# Cyclone-Pulse-Wrangler-Mainboard.net
KiCad netlist of a schematic drawn in EAGLE
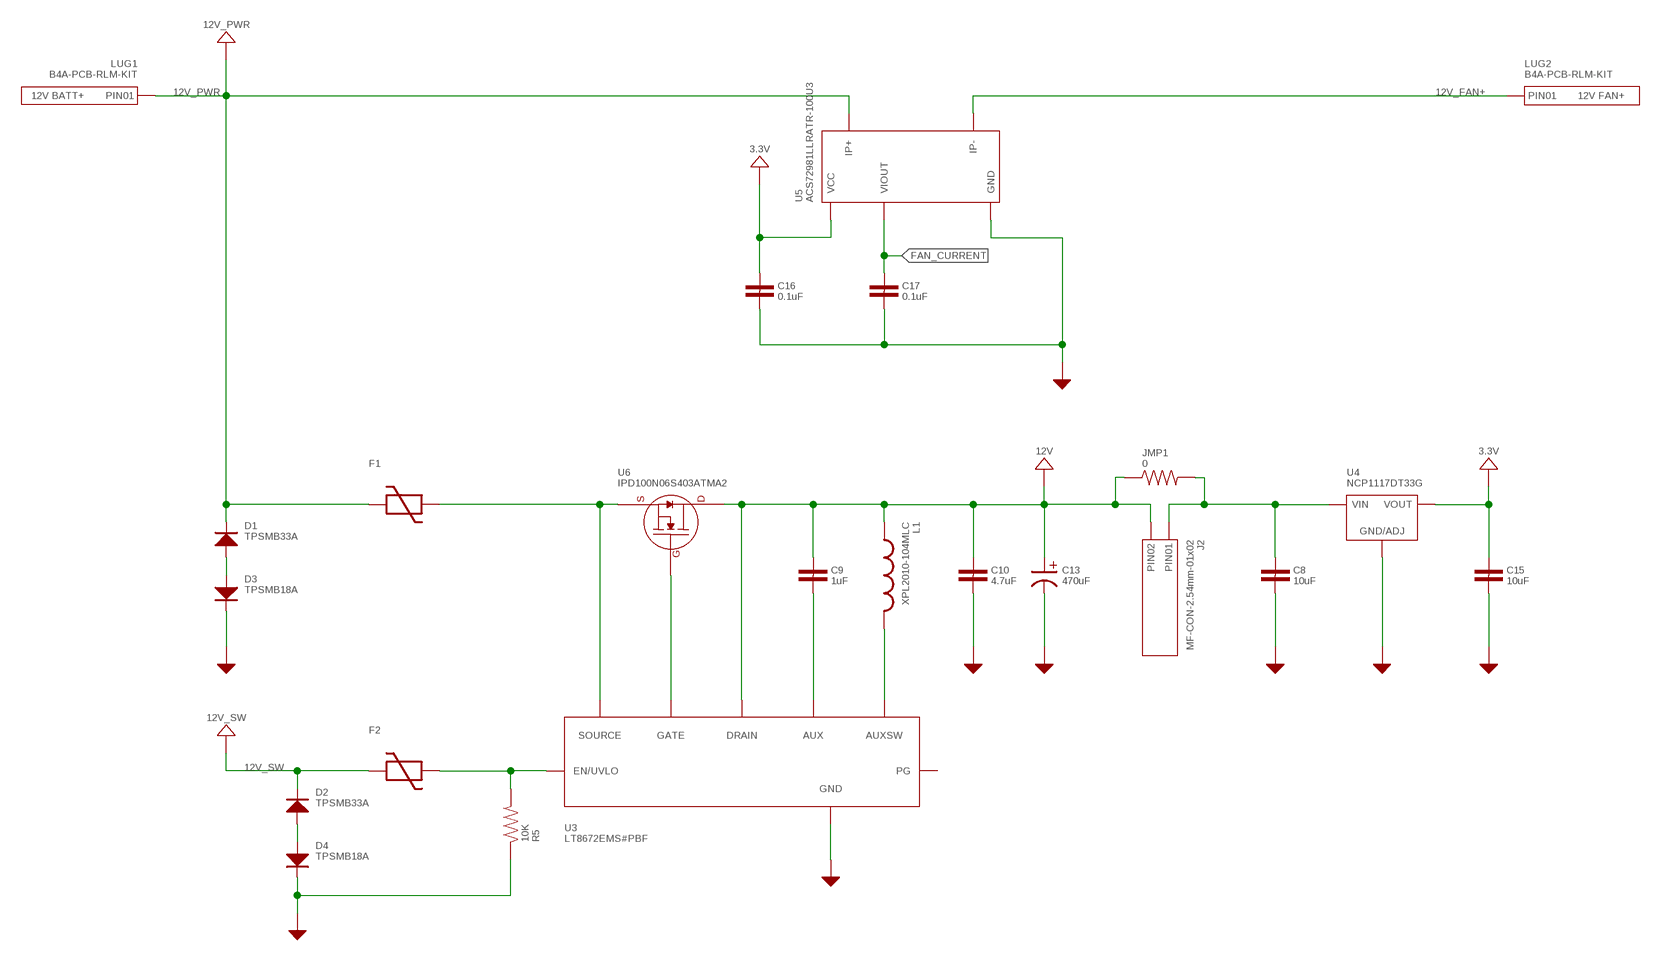
[diagram p0: schematic, sheet 1, part 1 of 3]
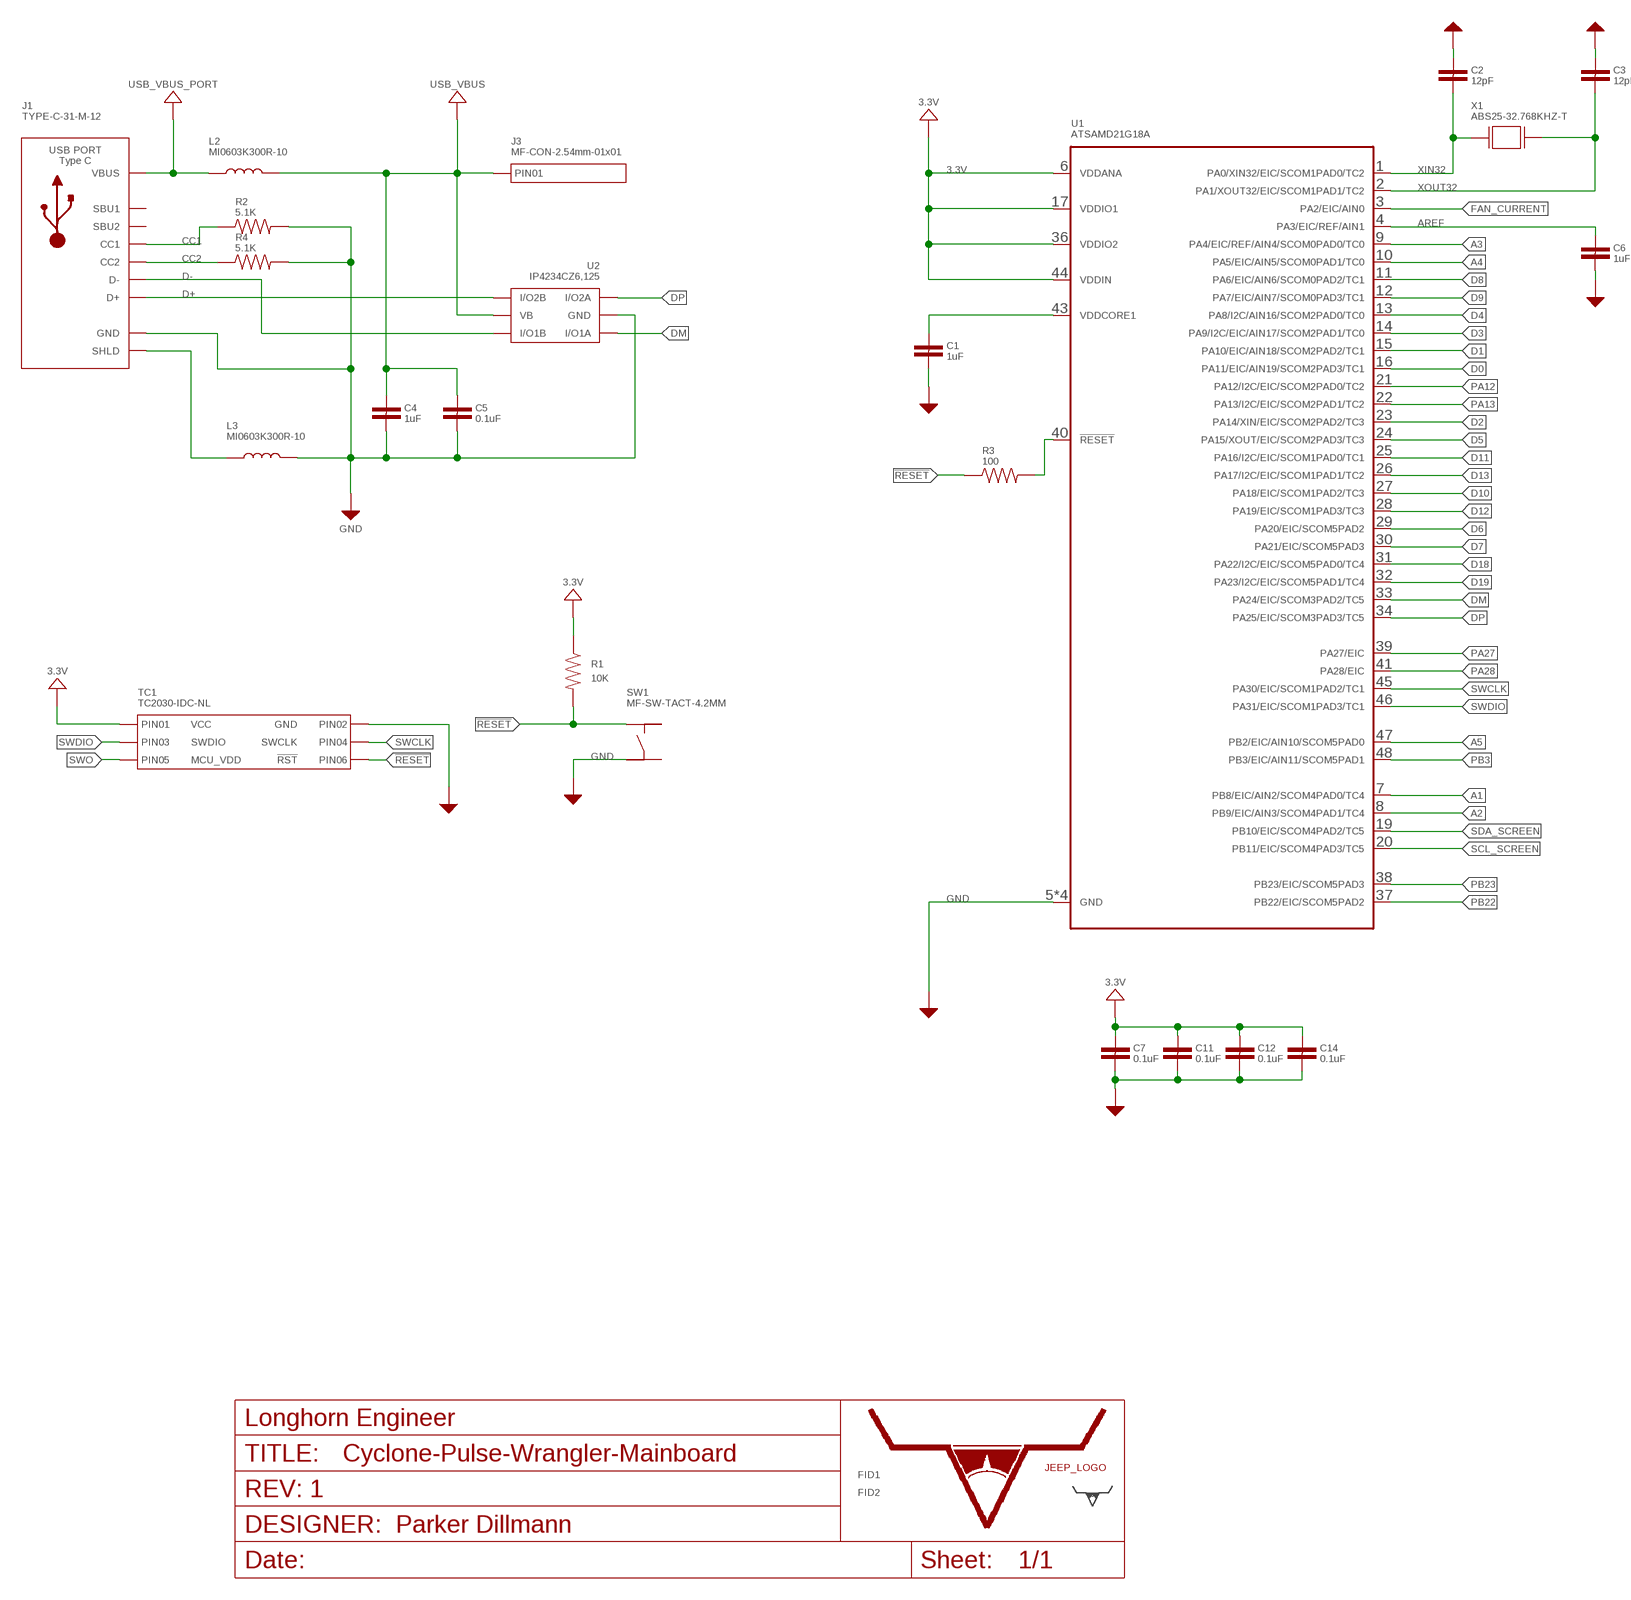
[diagram p1: schematic, sheet 1, part 2 of 3]
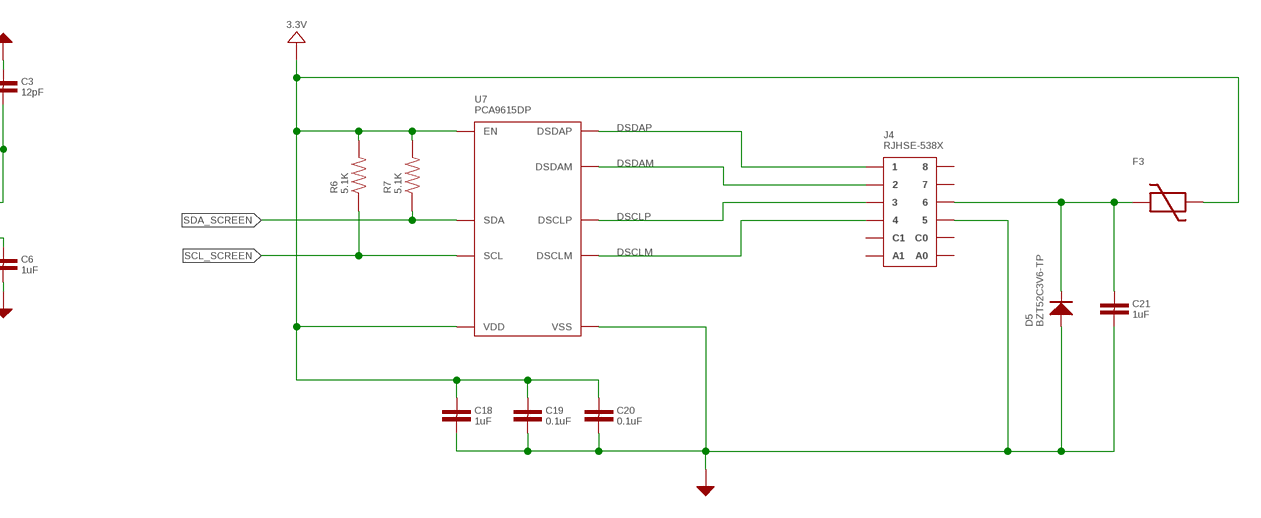
[diagram p2: schematic, sheet 1, part 3 of 3]

(export (version "E")
  (design (tool "Eeschema 10.0.6"))
  (components
    (comp (ref "C1")
      (value "1uF")
      (footprint "eagle-import:0805")
      (fields (field (name "MPN") "C0805X105K5RACAUTO"))
      (libsource (lib "eagle-import") (part "CAPACITOR_NON_POLAR_0805"))
    )
    (comp (ref "C2")
      (value "12pF")
      (footprint "eagle-import:0805")
      (fields (field (name "MPN") "C0805X105K5RACAUTO"))
      (libsource (lib "eagle-import") (part "CAPACITOR_NON_POLAR_0805"))
    )
    (comp (ref "C3")
      (value "12pF")
      (footprint "eagle-import:0805")
      (fields (field (name "MPN") "C0805X105K5RACAUTO"))
      (libsource (lib "eagle-import") (part "CAPACITOR_NON_POLAR_0805"))
    )
    (comp (ref "C4")
      (value "1uF")
      (footprint "eagle-import:0805")
      (fields (field (name "MPN") "C0805X105K5RACAUTO"))
      (libsource (lib "eagle-import") (part "CAPACITOR_NON_POLAR_0805"))
    )
    (comp (ref "C5")
      (value "0.1uF")
      (footprint "eagle-import:0805")
      (libsource (lib "eagle-import") (part "CAPACITOR_NON_POLAR_0805"))
    )
    (comp (ref "C6")
      (value "1uF")
      (footprint "eagle-import:0805")
      (fields (field (name "MPN") "C0805X105K5RACAUTO"))
      (libsource (lib "eagle-import") (part "CAPACITOR_NON_POLAR_0805"))
    )
    (comp (ref "C7")
      (value "0.1uF")
      (footprint "eagle-import:0805")
      (libsource (lib "eagle-import") (part "CAPACITOR_NON_POLAR_0805"))
    )
    (comp (ref "C8")
      (value "10uF")
      (footprint "eagle-import:1210")
      (libsource (lib "eagle-import") (part "CAPACITOR_NON_POLAR_1210"))
    )
    (comp (ref "C9")
      (value "1uF")
      (footprint "eagle-import:0805")
      (fields (field (name "MPN") "C0805X105K5RACAUTO"))
      (libsource (lib "eagle-import") (part "CAPACITOR_NON_POLAR_0805"))
    )
    (comp (ref "C10")
      (value "4.7uF")
      (footprint "eagle-import:1210")
      (fields (field (name "MPN") "UMJ325AB7475KMHP"))
      (libsource (lib "eagle-import") (part "CAPACITOR_NON_POLAR_1210"))
    )
    (comp (ref "C11")
      (value "0.1uF")
      (footprint "eagle-import:0805")
      (libsource (lib "eagle-import") (part "CAPACITOR_NON_POLAR_0805"))
    )
    (comp (ref "C12")
      (value "0.1uF")
      (footprint "eagle-import:0805")
      (libsource (lib "eagle-import") (part "CAPACITOR_NON_POLAR_0805"))
    )
    (comp (ref "C13")
      (value "470uF")
      (footprint "eagle-import:10MM_CAP_SMD")
      (fields (field (name "MPN") "EEH-ZS1V471P"))
      (libsource (lib "eagle-import") (part "CAPACITOR_POLARIZED_10MM_SMD"))
    )
    (comp (ref "C14")
      (value "0.1uF")
      (footprint "eagle-import:0805")
      (libsource (lib "eagle-import") (part "CAPACITOR_NON_POLAR_0805"))
    )
    (comp (ref "C15")
      (value "10uF")
      (footprint "eagle-import:1210")
      (libsource (lib "eagle-import") (part "CAPACITOR_NON_POLAR_1210"))
    )
    (comp (ref "C16")
      (value "0.1uF")
      (footprint "eagle-import:0805")
      (libsource (lib "eagle-import") (part "CAPACITOR_NON_POLAR_0805"))
    )
    (comp (ref "C17")
      (value "0.1uF")
      (footprint "eagle-import:0805")
      (libsource (lib "eagle-import") (part "CAPACITOR_NON_POLAR_0805"))
    )
    (comp (ref "C18")
      (value "1uF")
      (footprint "eagle-import:0805")
      (fields (field (name "MPN") "C0805X105K5RACAUTO"))
      (libsource (lib "eagle-import") (part "CAPACITOR_NON_POLAR_0805"))
    )
    (comp (ref "C19")
      (value "0.1uF")
      (footprint "eagle-import:0805")
      (libsource (lib "eagle-import") (part "CAPACITOR_NON_POLAR_0805"))
    )
    (comp (ref "C20")
      (value "0.1uF")
      (footprint "eagle-import:0805")
      (libsource (lib "eagle-import") (part "CAPACITOR_NON_POLAR_0805"))
    )
    (comp (ref "C21")
      (value "1uF")
      (footprint "eagle-import:0805")
      (fields (field (name "MPN") "C0805X105K5RACAUTO"))
      (libsource (lib "eagle-import") (part "CAPACITOR_NON_POLAR_0805"))
    )
    (comp (ref "D1")
      (value "TPSMB33A")
      (footprint "eagle-import:DO-214AA")
      (libsource (lib "eagle-import") (part "DIODE_DO-214AA"))
    )
    (comp (ref "D2")
      (value "TPSMB33A")
      (footprint "eagle-import:DO-214AA")
      (libsource (lib "eagle-import") (part "DIODE_DO-214AA"))
    )
    (comp (ref "D3")
      (value "TPSMB18A")
      (footprint "eagle-import:DO-214AA")
      (libsource (lib "eagle-import") (part "DIODE_DO-214AA"))
    )
    (comp (ref "D4")
      (value "TPSMB18A")
      (footprint "eagle-import:DO-214AA")
      (libsource (lib "eagle-import") (part "DIODE_DO-214AA"))
    )
    (comp (ref "D5")
      (value "BZT52C3V6-TP")
      (footprint "eagle-import:SOD-123")
      (libsource (lib "eagle-import") (part "DIODE_SOD-123"))
    )
    (comp (ref "F1")
      (value "PTC_FUSE_2920")
      (footprint "eagle-import:2920")
      (libsource (lib "eagle-import") (part "PTC_FUSE_2920"))
    )
    (comp (ref "F2")
      (value "PTC_FUSE_2920")
      (footprint "eagle-import:2920")
      (libsource (lib "eagle-import") (part "PTC_FUSE_2920"))
    )
    (comp (ref "F3")
      (value "PTC_FUSE_2920")
      (footprint "eagle-import:2920")
      (libsource (lib "eagle-import") (part "PTC_FUSE_2920"))
    )
    (comp (ref "FID1")
      (value "FIDUCIAL_0.5MM")
      (footprint "eagle-import:FIDUCIAL_0.5MM")
      (fields (field (name "HOUSEPART") "NO"))
      (libsource (lib "eagle-import") (part "FIDUCIAL_0.5MM"))
    )
    (comp (ref "FID2")
      (value "FIDUCIAL_0.5MM")
      (footprint "eagle-import:FIDUCIAL_0.5MM")
      (fields (field (name "HOUSEPART") "NO"))
      (libsource (lib "eagle-import") (part "FIDUCIAL_0.5MM"))
    )
    (comp (ref "J1")
      (value "TYPE-C-31-M-12")
      (footprint "eagle-import:TYPE-C-31-M-12")
      (libsource (lib "eagle-import") (part "USB_TYPE-C_MINIMAL"))
    )
    (comp (ref "J2")
      (value "MF-CON-2.54mm-01x02")
      (footprint "eagle-import:PTH_2.54MM_01X02")
      (fields (field (name "HOUSEPART") "YES"))
      (libsource (lib "eagle-import") (part "CON_01X02_PTH_2.54MM"))
    )
    (comp (ref "J3")
      (value "MF-CON-2.54mm-01x01")
      (footprint "eagle-import:PTH_2.54MM_01X01")
      (fields (field (name "HOUSEPART") "YES"))
      (libsource (lib "eagle-import") (part "CON_01X01_PTH_2.54MM"))
    )
    (comp (ref "J4")
      (value "RJHSE-538X")
      (footprint "eagle-import:RJHSE-538X")
      (libsource (lib "eagle-import") (part "RJ45_SINGLE_RJHSE-538X"))
    )
    (comp (ref "JMP1")
      (value "0")
      (footprint "eagle-import:R0603")
      (libsource (lib "eagle-import") (part "RESISTOR_0603"))
    )
    (comp (ref "L1")
      (value "XPL2010-104MLC")
      (footprint "eagle-import:XPL2010")
      (libsource (lib "eagle-import") (part "INDUCTOR_XPL2010"))
    )
    (comp (ref "L2")
      (value "MI0603K300R-10")
      (footprint "eagle-import:L0603")
      (fields (field (name "MPN") "MI0603K300R-10"))
      (libsource (lib "eagle-import") (part "INDUCTOR_0603"))
    )
    (comp (ref "L3")
      (value "MI0603K300R-10")
      (footprint "eagle-import:L0603")
      (fields (field (name "MPN") "MI0603K300R-10"))
      (libsource (lib "eagle-import") (part "INDUCTOR_0603"))
    )
    (comp (ref "LUG1")
      (value "B4A-PCB-RLM-KIT")
      (footprint "eagle-import:B4A-PCB-RLM")
      (fields (field (name "LABEL01") "12V BATT+"))
      (libsource (lib "eagle-import") (part "CON_01X01_B4A-PCB-RLM"))
    )
    (comp (ref "LUG2")
      (value "B4A-PCB-RLM-KIT")
      (footprint "eagle-import:B4A-PCB-RLM")
      (fields (field (name "LABEL01") "12V FAN+"))
      (libsource (lib "eagle-import") (part "CON_01X01_B4A-PCB-RLM"))
    )
    (comp (ref "R1")
      (value "10K")
      (footprint "eagle-import:R0603")
      (fields (field (name "MPN") "MF-RES-0603-10K"))
      (libsource (lib "eagle-import") (part "RESISTOR_0603"))
    )
    (comp (ref "R2")
      (value "5.1K")
      (footprint "eagle-import:R0603")
      (libsource (lib "eagle-import") (part "RESISTOR_0603"))
    )
    (comp (ref "R3")
      (value "100")
      (footprint "eagle-import:R0603")
      (fields (field (name "MPN") "MF-RES-0603-100"))
      (libsource (lib "eagle-import") (part "RESISTOR_0603"))
    )
    (comp (ref "R4")
      (value "5.1K")
      (footprint "eagle-import:R0603")
      (libsource (lib "eagle-import") (part "RESISTOR_0603"))
    )
    (comp (ref "R5")
      (value "10K")
      (footprint "eagle-import:R0603")
      (fields (field (name "MPN") "MF-RES-0603-10K"))
      (libsource (lib "eagle-import") (part "RESISTOR_0603"))
    )
    (comp (ref "R6")
      (value "5.1K")
      (footprint "eagle-import:R0603")
      (fields (field (name "MPN") "MF-RES-0603-100"))
      (libsource (lib "eagle-import") (part "RESISTOR_0603"))
    )
    (comp (ref "R7")
      (value "5.1K")
      (footprint "eagle-import:R0603")
      (fields (field (name "MPN") "MF-RES-0603-100"))
      (libsource (lib "eagle-import") (part "RESISTOR_0603"))
    )
    (comp (ref "SW1")
      (value "MF-SW-TACT-4.2MM")
      (footprint "eagle-import:TACT4.2MM")
      (fields (field (name "HOUSEPART") "YES"))
      (libsource (lib "eagle-import") (part "TACT_4.2MM"))
    )
    (comp (ref "TC1")
      (value "TC2030-IDC-NL")
      (footprint "eagle-import:TC2030-IDC-NL")
      (fields
        (field (name "HOUSEPART") "NO")
        (field (name "LABEL01") "VCC")
        (field (name "LABEL02") "GND")
        (field (name "LABEL03") "SWDIO")
        (field (name "LABEL04") "SWCLK")
        (field (name "LABEL05") "MCU_VDD")
        (field (name "LABEL06") "!RST")
      )
      (libsource (lib "eagle-import") (part "CON_02X03_TC2030-IDC-NL_SWD2TC"))
    )
    (comp (ref "U$1")
      (value "LHE_FRAME")
      (footprint "eagle-import:LHE_FRAME")
      (fields (field (name "DNAME") "Parker Dillmann") (field (name "REVNUM") "REV: 1"))
      (libsource (lib "eagle-import") (part "LHE_FRAME"))
    )
    (comp (ref "U$35")
      (value "JEEP_LOGO_SILK_MEDIUM")
      (footprint "eagle-import:JEEP_SILK_MEDIUM")
      (libsource (lib "eagle-import") (part "JEEP_LOGO_SILK_MEDIUM"))
    )
    (comp (ref "U$42")
      (value "LHE_LOGOLHE_LOGO")
      (footprint "eagle-import:LHE_LOGO")
      (libsource (lib "eagle-import") (part "LHE_LOGOLHE_LOGO"))
    )
    (comp (ref "U1")
      (value "ATSAMD21G18A")
      (footprint "eagle-import:ATSAMD21G18A_TQFP-48")
      (fields (field (name "MPN") "ATSAMD21G18A-AU"))
      (libsource (lib "eagle-import") (part "ATSAMD21G18A-AU"))
    )
    (comp (ref "U2")
      (value "IP4234CZ6,125")
      (footprint "eagle-import:IP4234CZ6_SOT-457-6")
      (libsource (lib "eagle-import") (part "IP4234CZ6"))
    )
    (comp (ref "U3")
      (value "LT8672EMS#PBF")
      (footprint "eagle-import:LT8672_MSOP-10")
      (libsource (lib "eagle-import") (part "LT8672EMS#PBF"))
    )
    (comp (ref "U4")
      (value "NCP1117DT33G")
      (footprint "eagle-import:NCP1117DT_DPAK-3")
      (libsource (lib "eagle-import") (part "LINEAR_VOTLAGE_REGULATORS_NCP1117DT"))
    )
    (comp (ref "U5")
      (value "ACS72981LLRATR-100U3")
      (footprint "eagle-import:ACS72981_PSOF-7")
      (libsource (lib "eagle-import") (part "ACS72981"))
    )
    (comp (ref "U6")
      (value "IPD100N06S403ATMA2")
      (footprint "eagle-import:TO-252-3")
      (libsource (lib "eagle-import") (part "MOSFET_N-CHANNEL_SINGLE_TO-252-3"))
    )
    (comp (ref "U7")
      (value "PCA9615DP")
      (footprint "eagle-import:PCA9615DP_TSSOP-10")
      (libsource (lib "eagle-import") (part "PCA9615DP"))
    )
    (comp (ref "X1")
      (value "ABS25-32.768KHZ-T")
      (footprint "eagle-import:ABS25_SERIES")
      (fields (field (name "HOUSEPART") "NO") (field (name "MPN") "ABS25-32.768KHZ-T "))
      (libsource (lib "eagle-import") (part "CYRSTAL_ABS25"))
    )
  )
  (nets
    (net (code "1") (name "/12V_FAN+") (class "Default")
      (node (ref "LUG2") (pin "P$1") (pinfunction "PIN1_P$1") (pintype "bidirectional"))
      (node (ref "LUG2") (pin "P$2") (pinfunction "PIN1_P$2") (pintype "bidirectional"))
      (node (ref "U5") (pin "P$6") (pinfunction "IP-_P$6") (pintype "bidirectional"))
    )
    (net (code "2") (name "/AREF") (class "Default")
      (node (ref "C6") (pin "1") (pinfunction "1_1") (pintype "passive"))
      (node (ref "U1") (pin "4") (pinfunction "PA3/EIC/REF/AIN1_4") (pintype "bidirectional"))
    )
    (net (code "3") (name "/CC1") (class "Default")
      (node (ref "J1") (pin "A5") (pinfunction "CC1_A5") (pintype "bidirectional"))
      (node (ref "R2") (pin "P$1") (pinfunction "P$1_P$1") (pintype "passive"))
    )
    (net (code "4") (name "/CC2") (class "Default")
      (node (ref "J1") (pin "B5") (pinfunction "CC2_B5") (pintype "bidirectional"))
      (node (ref "R4") (pin "P$1") (pinfunction "P$1_P$1") (pintype "passive"))
    )
    (net (code "5") (name "/D+") (class "Default")
      (node (ref "J1") (pin "A6") (pinfunction "D+_A6") (pintype "bidirectional"))
      (node (ref "J1") (pin "B6") (pinfunction "D+_B6") (pintype "bidirectional"))
      (node (ref "U2") (pin "4") (pinfunction "I/O2B_4") (pintype "bidirectional"))
    )
    (net (code "6") (name "/D-") (class "Default")
      (node (ref "J1") (pin "A7") (pinfunction "D-_A7") (pintype "bidirectional"))
      (node (ref "J1") (pin "B7") (pinfunction "D-_B7") (pintype "bidirectional"))
      (node (ref "U2") (pin "3") (pinfunction "I/O1B_3") (pintype "bidirectional"))
    )
    (net (code "7") (name "/DSCLM") (class "Default")
      (node (ref "J4") (pin "4") (pinfunction "4_4") (pintype "bidirectional"))
      (node (ref "U7") (pin "P$6") (pinfunction "DSCLM_P$6") (pintype "bidirectional"))
    )
    (net (code "8") (name "/DSCLP") (class "Default")
      (node (ref "J4") (pin "3") (pinfunction "3_3") (pintype "bidirectional"))
      (node (ref "U7") (pin "P$7") (pinfunction "DSCLP_P$7") (pintype "bidirectional"))
    )
    (net (code "9") (name "/DSDAM") (class "Default")
      (node (ref "J4") (pin "2") (pinfunction "2_2") (pintype "bidirectional"))
      (node (ref "U7") (pin "P$9") (pinfunction "DSDAM_P$9") (pintype "bidirectional"))
    )
    (net (code "10") (name "/DSDAP") (class "Default")
      (node (ref "J4") (pin "1") (pinfunction "1_1") (pintype "bidirectional"))
      (node (ref "U7") (pin "P$8") (pinfunction "DSDAP_P$8") (pintype "bidirectional"))
    )
    (net (code "11") (name "/XIN32") (class "Default")
      (node (ref "C2") (pin "2") (pinfunction "2_2") (pintype "passive"))
      (node (ref "U1") (pin "1") (pinfunction "PA0/XIN32/EIC/SCOM1PAD0/TC2_1") (pintype "bidirectional"))
      (node (ref "X1") (pin "1") (pinfunction "X0_1") (pintype "bidirectional"))
    )
    (net (code "12") (name "/XOUT32") (class "Default")
      (node (ref "C3") (pin "2") (pinfunction "2_2") (pintype "passive"))
      (node (ref "U1") (pin "2") (pinfunction "PA1/XOUT32/EIC/SCOM1PAD1/TC2_2") (pintype "bidirectional"))
      (node (ref "X1") (pin "4") (pinfunction "X1_4") (pintype "bidirectional"))
    )
    (net (code "13") (name "/~{RESET}") (class "Default")
      (node (ref "R1") (pin "P$2") (pinfunction "P$2_P$2") (pintype "passive"))
      (node (ref "R3") (pin "P$1") (pinfunction "P$1_P$1") (pintype "passive"))
      (node (ref "SW1") (pin "P$1") (pinfunction "P$1_P$1") (pintype "bidirectional"))
      (node (ref "TC1") (pin "P$6") (pinfunction "PIN6_P$6") (pintype "bidirectional"))
    )
    (net (code "14") (name "3.3V") (class "Default")
      (node (ref "C11") (pin "1") (pinfunction "1_1") (pintype "passive"))
      (node (ref "C12") (pin "1") (pinfunction "1_1") (pintype "passive"))
      (node (ref "C14") (pin "1") (pinfunction "1_1") (pintype "passive"))
      (node (ref "C15") (pin "1") (pinfunction "1_1") (pintype "passive"))
      (node (ref "C16") (pin "1") (pinfunction "1_1") (pintype "passive"))
      (node (ref "C18") (pin "1") (pinfunction "1_1") (pintype "passive"))
      (node (ref "C19") (pin "1") (pinfunction "1_1") (pintype "passive"))
      (node (ref "C20") (pin "1") (pinfunction "1_1") (pintype "passive"))
      (node (ref "C7") (pin "1") (pinfunction "1_1") (pintype "passive"))
      (node (ref "F3") (pin "2") (pinfunction "P$2_2") (pintype "bidirectional"))
      (node (ref "R1") (pin "P$1") (pinfunction "P$1_P$1") (pintype "passive"))
      (node (ref "R6") (pin "P$2") (pinfunction "P$2_P$2") (pintype "passive"))
      (node (ref "R7") (pin "P$2") (pinfunction "P$2_P$2") (pintype "passive"))
      (node (ref "TC1") (pin "P$1") (pinfunction "PIN1_P$1") (pintype "bidirectional"))
      (node (ref "U1") (pin "17") (pinfunction "VDDIO1_17") (pintype "bidirectional"))
      (node (ref "U1") (pin "36") (pinfunction "VDDIO2_36") (pintype "bidirectional"))
      (node (ref "U1") (pin "44") (pinfunction "VDDIN_44") (pintype "bidirectional"))
      (node (ref "U1") (pin "6") (pinfunction "VDDANA_6") (pintype "bidirectional"))
      (node (ref "U4") (pin "TAB") (pinfunction "OUT_TAB") (pintype "bidirectional"))
      (node (ref "U5") (pin "P$1") (pinfunction "VCC_P$1") (pintype "bidirectional"))
      (node (ref "U7") (pin "P$1") (pinfunction "VDD_P$1") (pintype "bidirectional"))
      (node (ref "U7") (pin "P$10") (pinfunction "VDD_P$10") (pintype "bidirectional"))
      (node (ref "U7") (pin "P$3") (pinfunction "EN_P$3") (pintype "bidirectional"))
    )
    (net (code "15") (name "12V") (class "Default")
      (node (ref "C10") (pin "1") (pinfunction "1_1") (pintype "passive"))
      (node (ref "C13") (pin "POS") (pinfunction "POS_POS") (pintype "bidirectional"))
      (node (ref "C9") (pin "1") (pinfunction "1_1") (pintype "passive"))
      (node (ref "J2") (pin "P$2") (pinfunction "PIN2_P$2") (pintype "bidirectional"))
      (node (ref "JMP1") (pin "P$1") (pinfunction "P$1_P$1") (pintype "passive"))
      (node (ref "L1") (pin "P$1") (pinfunction "P$1_P$1") (pintype "bidirectional"))
      (node (ref "U3") (pin "8") (pinfunction "DRAIN_8") (pintype "bidirectional"))
      (node (ref "U6") (pin "PAD") (pinfunction "DRAIN_PAD") (pintype "bidirectional"))
    )
    (net (code "16") (name "12V_PWR") (class "Default")
      (node (ref "D1") (pin "C") (pinfunction "CATHODE_C") (pintype "bidirectional"))
      (node (ref "F1") (pin "1") (pinfunction "P$1_1") (pintype "bidirectional"))
      (node (ref "LUG1") (pin "P$1") (pinfunction "PIN1_P$1") (pintype "bidirectional"))
      (node (ref "LUG1") (pin "P$2") (pinfunction "PIN1_P$2") (pintype "bidirectional"))
      (node (ref "U5") (pin "P$5") (pinfunction "IP+_P$5") (pintype "bidirectional"))
    )
    (net (code "17") (name "12V_SW") (class "Default")
      (node (ref "D2") (pin "C") (pinfunction "CATHODE_C") (pintype "bidirectional"))
      (node (ref "F2") (pin "1") (pinfunction "P$1_1") (pintype "bidirectional"))
    )
    (net (code "18") (name "A1") (class "Default")
      (node (ref "U1") (pin "7") (pinfunction "PB8/EIC/AIN2/SCOM4PAD0/TC4_7") (pintype "bidirectional"))
    )
    (net (code "19") (name "A2") (class "Default")
      (node (ref "U1") (pin "8") (pinfunction "PB9/EIC/AIN3/SCOM4PAD1/TC4_8") (pintype "bidirectional"))
    )
    (net (code "20") (name "A3") (class "Default")
      (node (ref "U1") (pin "9") (pinfunction "PA4/EIC/REF/AIN4/SCOM0PAD0/TC0_9") (pintype "bidirectional"))
    )
    (net (code "21") (name "A4") (class "Default")
      (node (ref "U1") (pin "10") (pinfunction "PA5/EIC/AIN5/SCOM0PAD1/TC0_10") (pintype "bidirectional"))
    )
    (net (code "22") (name "A5") (class "Default")
      (node (ref "U1") (pin "47") (pinfunction "PB2/EIC/AIN10/SCOM5PAD0_47") (pintype "bidirectional"))
    )
    (net (code "23") (name "D0") (class "Default")
      (node (ref "U1") (pin "16") (pinfunction "PA11/EIC/AIN19/SCOM2PAD3/TC1_16") (pintype "bidirectional"))
    )
    (net (code "24") (name "D1") (class "Default")
      (node (ref "U1") (pin "15") (pinfunction "PA10/EIC/AIN18/SCOM2PAD2/TC1_15") (pintype "bidirectional"))
    )
    (net (code "25") (name "D2") (class "Default")
      (node (ref "U1") (pin "23") (pinfunction "PA14/XIN/EIC/SCOM2PAD2/TC3_23") (pintype "bidirectional"))
    )
    (net (code "26") (name "D3") (class "Default")
      (node (ref "U1") (pin "14") (pinfunction "PA9/I2C/EIC/AIN17/SCOM2PAD1/TC0_14") (pintype "bidirectional"))
    )
    (net (code "27") (name "D4") (class "Default")
      (node (ref "U1") (pin "13") (pinfunction "PA8/I2C/AIN16/SCOM2PAD0/TC0_13") (pintype "bidirectional"))
    )
    (net (code "28") (name "D5") (class "Default")
      (node (ref "U1") (pin "24") (pinfunction "PA15/XOUT/EIC/SCOM2PAD3/TC3_24") (pintype "bidirectional"))
    )
    (net (code "29") (name "D6") (class "Default")
      (node (ref "U1") (pin "29") (pinfunction "PA20/EIC/SCOM5PAD2_29") (pintype "bidirectional"))
    )
    (net (code "30") (name "D7") (class "Default")
      (node (ref "U1") (pin "30") (pinfunction "PA21/EIC/SCOM5PAD3_30") (pintype "bidirectional"))
    )
    (net (code "31") (name "D8") (class "Default")
      (node (ref "U1") (pin "11") (pinfunction "PA6/EIC/AIN6/SCOM0PAD2/TC1_11") (pintype "bidirectional"))
    )
    (net (code "32") (name "D9") (class "Default")
      (node (ref "U1") (pin "12") (pinfunction "PA7/EIC/AIN7/SCOM0PAD3/TC1_12") (pintype "bidirectional"))
    )
    (net (code "33") (name "D10") (class "Default")
      (node (ref "U1") (pin "27") (pinfunction "PA18/EIC/SCOM1PAD2/TC3_27") (pintype "bidirectional"))
    )
    (net (code "34") (name "D11") (class "Default")
      (node (ref "U1") (pin "25") (pinfunction "PA16/I2C/EIC/SCOM1PAD0/TC1_25") (pintype "bidirectional"))
    )
    (net (code "35") (name "D12") (class "Default")
      (node (ref "U1") (pin "28") (pinfunction "PA19/EIC/SCOM1PAD3/TC3_28") (pintype "bidirectional"))
    )
    (net (code "36") (name "D13") (class "Default")
      (node (ref "U1") (pin "26") (pinfunction "PA17/I2C/EIC/SCOM1PAD1/TC2_26") (pintype "bidirectional"))
    )
    (net (code "37") (name "D18") (class "Default")
      (node (ref "U1") (pin "31") (pinfunction "PA22/I2C/EIC/SCOM5PAD0/TC4_31") (pintype "bidirectional"))
    )
    (net (code "38") (name "D19") (class "Default")
      (node (ref "U1") (pin "32") (pinfunction "PA23/I2C/EIC/SCOM5PAD1/TC4_32") (pintype "bidirectional"))
    )
    (net (code "39") (name "DM") (class "Default")
      (node (ref "U1") (pin "33") (pinfunction "PA24/EIC/SCOM3PAD2/TC5_33") (pintype "bidirectional"))
      (node (ref "U2") (pin "1") (pinfunction "I/O1A_1") (pintype "bidirectional"))
    )
    (net (code "40") (name "DP") (class "Default")
      (node (ref "U1") (pin "34") (pinfunction "PA25/EIC/SCOM3PAD3/TC5_34") (pintype "bidirectional"))
      (node (ref "U2") (pin "6") (pinfunction "I/O2A_6") (pintype "bidirectional"))
    )
    (net (code "41") (name "FAN_CURRENT") (class "Default")
      (node (ref "C17") (pin "1") (pinfunction "1_1") (pintype "passive"))
      (node (ref "U1") (pin "3") (pinfunction "PA2/EIC/AIN0_3") (pintype "bidirectional"))
      (node (ref "U5") (pin "P$3") (pinfunction "VIOUT_P$3") (pintype "bidirectional"))
    )
    (net (code "42") (name "GND") (class "Default")
      (node (ref "C1") (pin "2") (pinfunction "2_2") (pintype "passive"))
      (node (ref "C10") (pin "2") (pinfunction "2_2") (pintype "passive"))
      (node (ref "C11") (pin "2") (pinfunction "2_2") (pintype "passive"))
      (node (ref "C12") (pin "2") (pinfunction "2_2") (pintype "passive"))
      (node (ref "C13") (pin "NEG") (pinfunction "NEG_NEG") (pintype "bidirectional"))
      (node (ref "C14") (pin "2") (pinfunction "2_2") (pintype "passive"))
      (node (ref "C15") (pin "2") (pinfunction "2_2") (pintype "passive"))
      (node (ref "C16") (pin "2") (pinfunction "2_2") (pintype "passive"))
      (node (ref "C17") (pin "2") (pinfunction "2_2") (pintype "passive"))
      (node (ref "C18") (pin "2") (pinfunction "2_2") (pintype "passive"))
      (node (ref "C19") (pin "2") (pinfunction "2_2") (pintype "passive"))
      (node (ref "C2") (pin "1") (pinfunction "1_1") (pintype "passive"))
      (node (ref "C20") (pin "2") (pinfunction "2_2") (pintype "passive"))
      (node (ref "C21") (pin "2") (pinfunction "2_2") (pintype "passive"))
      (node (ref "C3") (pin "1") (pinfunction "1_1") (pintype "passive"))
      (node (ref "C4") (pin "2") (pinfunction "2_2") (pintype "passive"))
      (node (ref "C5") (pin "2") (pinfunction "2_2") (pintype "passive"))
      (node (ref "C6") (pin "2") (pinfunction "2_2") (pintype "passive"))
      (node (ref "C7") (pin "2") (pinfunction "2_2") (pintype "passive"))
      (node (ref "C8") (pin "2") (pinfunction "2_2") (pintype "passive"))
      (node (ref "D3") (pin "C") (pinfunction "CATHODE_C") (pintype "bidirectional"))
      (node (ref "D4") (pin "C") (pinfunction "CATHODE_C") (pintype "bidirectional"))
      (node (ref "D5") (pin "2") (pinfunction "ANODE_2") (pintype "bidirectional"))
      (node (ref "J1") (pin "A1/B12") (pinfunction "GND_A1/B12") (pintype "bidirectional"))
      (node (ref "J1") (pin "B1/A12") (pinfunction "GND_B1/A12") (pintype "bidirectional"))
      (node (ref "J4") (pin "5") (pinfunction "5_5") (pintype "bidirectional"))
      (node (ref "L3") (pin "P$2") (pinfunction "P$2_P$2") (pintype "passive"))
      (node (ref "R2") (pin "P$2") (pinfunction "P$2_P$2") (pintype "passive"))
      (node (ref "R4") (pin "P$2") (pinfunction "P$2_P$2") (pintype "passive"))
      (node (ref "R5") (pin "P$1") (pinfunction "P$1_P$1") (pintype "passive"))
      (node (ref "SW1") (pin "P$3") (pinfunction "P$3_P$3") (pintype "bidirectional"))
      (node (ref "TC1") (pin "P$2") (pinfunction "PIN2_P$2") (pintype "bidirectional"))
      (node (ref "U1") (pin "18") (pinfunction "GND_18") (pintype "bidirectional"))
      (node (ref "U1") (pin "35") (pinfunction "GND_35") (pintype "bidirectional"))
      (node (ref "U1") (pin "42") (pinfunction "GND_42") (pintype "bidirectional"))
      (node (ref "U1") (pin "5") (pinfunction "GND_5") (pintype "bidirectional"))
      (node (ref "U2") (pin "2") (pinfunction "GND_2") (pintype "bidirectional"))
      (node (ref "U3") (pin "2") (pinfunction "GND_2") (pintype "bidirectional"))
      (node (ref "U3") (pin "4") (pinfunction "GND_4") (pintype "bidirectional"))
      (node (ref "U4") (pin "1") (pinfunction "GND_1") (pintype "bidirectional"))
      (node (ref "U5") (pin "P$2") (pinfunction "GND_P$2") (pintype "bidirectional"))
      (node (ref "U5") (pin "P$4") (pinfunction "GND_P$4") (pintype "bidirectional"))
      (node (ref "U5") (pin "P$7") (pinfunction "GND_P$7") (pintype "bidirectional"))
      (node (ref "U7") (pin "P$5") (pinfunction "VSS_P$5") (pintype "bidirectional"))
    )
    (net (code "43") (name "Net-(D1-ANODE)") (class "Default")
      (node (ref "D1") (pin "A") (pinfunction "ANODE_A") (pintype "bidirectional"))
      (node (ref "D3") (pin "A") (pinfunction "ANODE_A") (pintype "bidirectional"))
    )
    (net (code "44") (name "Net-(D2-ANODE)") (class "Default")
      (node (ref "D2") (pin "A") (pinfunction "ANODE_A") (pintype "bidirectional"))
      (node (ref "D4") (pin "A") (pinfunction "ANODE_A") (pintype "bidirectional"))
    )
    (net (code "45") (name "Net-(D5-CATHODE)") (class "Default")
      (node (ref "C21") (pin "1") (pinfunction "1_1") (pintype "passive"))
      (node (ref "D5") (pin "1") (pinfunction "CATHODE_1") (pintype "bidirectional"))
      (node (ref "F3") (pin "1") (pinfunction "P$1_1") (pintype "bidirectional"))
      (node (ref "J4") (pin "6") (pinfunction "6_6") (pintype "bidirectional"))
    )
    (net (code "46") (name "Net-(F1-P$2)") (class "Default")
      (node (ref "F1") (pin "2") (pinfunction "P$2_2") (pintype "bidirectional"))
      (node (ref "U3") (pin "9") (pinfunction "SOURCE_9") (pintype "bidirectional"))
      (node (ref "U6") (pin "3") (pinfunction "SOURCE_3") (pintype "bidirectional"))
    )
    (net (code "47") (name "Net-(F2-P$2)") (class "Default")
      (node (ref "F2") (pin "2") (pinfunction "P$2_2") (pintype "bidirectional"))
      (node (ref "R5") (pin "P$2") (pinfunction "P$2_P$2") (pintype "passive"))
      (node (ref "U3") (pin "1") (pinfunction "EN/UVLO_1") (pintype "bidirectional"))
    )
    (net (code "48") (name "Net-(J1-SHLD-PadMT_B_0)") (class "Default")
      (node (ref "J1") (pin "MT_B_0") (pinfunction "SHLD_MT_B_0") (pintype "bidirectional"))
      (node (ref "J1") (pin "MT_B_1") (pinfunction "SHLD_MT_B_1") (pintype "bidirectional"))
      (node (ref "J1") (pin "MT_B_2") (pinfunction "SHLD_MT_B_2") (pintype "bidirectional"))
      (node (ref "J1") (pin "MT_B_3") (pinfunction "SHLD_MT_B_3") (pintype "bidirectional"))
      (node (ref "J1") (pin "MT_T_0") (pinfunction "SHLD_MT_T_0") (pintype "bidirectional"))
      (node (ref "J1") (pin "MT_T_1") (pinfunction "SHLD_MT_T_1") (pintype "bidirectional"))
      (node (ref "J1") (pin "MT_T_2") (pinfunction "SHLD_MT_T_2") (pintype "bidirectional"))
      (node (ref "J1") (pin "MT_T_3") (pinfunction "SHLD_MT_T_3") (pintype "bidirectional"))
      (node (ref "L3") (pin "P$1") (pinfunction "P$1_P$1") (pintype "passive"))
    )
    (net (code "49") (name "Net-(J2-PIN1)") (class "Default")
      (node (ref "C8") (pin "1") (pinfunction "1_1") (pintype "passive"))
      (node (ref "J2") (pin "P$1") (pinfunction "PIN1_P$1") (pintype "bidirectional"))
      (node (ref "JMP1") (pin "P$2") (pinfunction "P$2_P$2") (pintype "passive"))
      (node (ref "U4") (pin "3") (pinfunction "IN_3") (pintype "bidirectional"))
    )
    (net (code "50") (name "Net-(U1-VDDCORE1)") (class "Default")
      (node (ref "C1") (pin "1") (pinfunction "1_1") (pintype "passive"))
      (node (ref "U1") (pin "43") (pinfunction "VDDCORE1_43") (pintype "bidirectional"))
    )
    (net (code "51") (name "Net-(U1-~{RESET})") (class "Default")
      (node (ref "R3") (pin "P$2") (pinfunction "P$2_P$2") (pintype "passive"))
      (node (ref "U1") (pin "40") (pinfunction "~{RESET}_40") (pintype "bidirectional"))
    )
    (net (code "52") (name "Net-(U3-AUX)") (class "Default")
      (node (ref "C9") (pin "2") (pinfunction "2_2") (pintype "passive"))
      (node (ref "U3") (pin "7") (pinfunction "AUX_7") (pintype "bidirectional"))
    )
    (net (code "53") (name "Net-(U3-AUXSW)") (class "Default")
      (node (ref "L1") (pin "P$2") (pinfunction "P$2_P$2") (pintype "bidirectional"))
      (node (ref "U3") (pin "6") (pinfunction "AUXSW_6") (pintype "bidirectional"))
    )
    (net (code "54") (name "Net-(U3-GATE)") (class "Default")
      (node (ref "U3") (pin "10") (pinfunction "GATE_10") (pintype "bidirectional"))
      (node (ref "U6") (pin "1") (pinfunction "GATE_1") (pintype "bidirectional"))
    )
    (net (code "55") (name "PA12") (class "Default")
      (node (ref "U1") (pin "21") (pinfunction "PA12/I2C/EIC/SCOM2PAD0/TC2_21") (pintype "bidirectional"))
    )
    (net (code "56") (name "PA13") (class "Default")
      (node (ref "U1") (pin "22") (pinfunction "PA13/I2C/EIC/SCOM2PAD1/TC2_22") (pintype "bidirectional"))
    )
    (net (code "57") (name "PA27") (class "Default")
      (node (ref "U1") (pin "39") (pinfunction "PA27/EIC_39") (pintype "bidirectional"))
    )
    (net (code "58") (name "PA28") (class "Default")
      (node (ref "U1") (pin "41") (pinfunction "PA28/EIC_41") (pintype "bidirectional"))
    )
    (net (code "59") (name "PB3") (class "Default")
      (node (ref "U1") (pin "48") (pinfunction "PB3/EIC/AIN11/SCOM5PAD1_48") (pintype "bidirectional"))
    )
    (net (code "60") (name "PB22") (class "Default")
      (node (ref "U1") (pin "37") (pinfunction "PB22/EIC/SCOM5PAD2_37") (pintype "bidirectional"))
    )
    (net (code "61") (name "PB23") (class "Default")
      (node (ref "U1") (pin "38") (pinfunction "PB23/EIC/SCOM5PAD3_38") (pintype "bidirectional"))
    )
    (net (code "62") (name "SCL_SCREEN") (class "Default")
      (node (ref "R6") (pin "P$1") (pinfunction "P$1_P$1") (pintype "passive"))
      (node (ref "U1") (pin "20") (pinfunction "PB11/EIC/SCOM4PAD3/TC5_20") (pintype "bidirectional"))
      (node (ref "U7") (pin "P$4") (pinfunction "SCL_P$4") (pintype "bidirectional"))
    )
    (net (code "63") (name "SDA_SCREEN") (class "Default")
      (node (ref "R7") (pin "P$1") (pinfunction "P$1_P$1") (pintype "passive"))
      (node (ref "U1") (pin "19") (pinfunction "PB10/EIC/SCOM4PAD2/TC5_19") (pintype "bidirectional"))
      (node (ref "U7") (pin "P$2") (pinfunction "SDA_P$2") (pintype "bidirectional"))
    )
    (net (code "64") (name "SWCLK") (class "Default")
      (node (ref "TC1") (pin "P$4") (pinfunction "PIN4_P$4") (pintype "bidirectional"))
      (node (ref "U1") (pin "45") (pinfunction "PA30/EIC/SCOM1PAD2/TC1_45") (pintype "bidirectional"))
    )
    (net (code "65") (name "SWDIO") (class "Default")
      (node (ref "TC1") (pin "P$3") (pinfunction "PIN3_P$3") (pintype "bidirectional"))
      (node (ref "U1") (pin "46") (pinfunction "PA31/EIC/SCOM1PAD3/TC1_46") (pintype "bidirectional"))
    )
    (net (code "66") (name "SWO") (class "Default")
      (node (ref "TC1") (pin "P$5") (pinfunction "PIN5_P$5") (pintype "bidirectional"))
    )
    (net (code "67") (name "USB_VBUS") (class "Default")
      (node (ref "C4") (pin "1") (pinfunction "1_1") (pintype "passive"))
      (node (ref "C5") (pin "1") (pinfunction "1_1") (pintype "passive"))
      (node (ref "J3") (pin "P$1") (pinfunction "PIN1_P$1") (pintype "bidirectional"))
      (node (ref "L2") (pin "P$2") (pinfunction "P$2_P$2") (pintype "passive"))
      (node (ref "U2") (pin "5") (pinfunction "VB_5") (pintype "bidirectional"))
    )
    (net (code "68") (name "USB_VBUS_PORT") (class "Default")
      (node (ref "J1") (pin "A4/B9") (pinfunction "VBUS_A4/B9") (pintype "bidirectional"))
      (node (ref "J1") (pin "B4/A9") (pinfunction "VBUS_B4/A9") (pintype "bidirectional"))
      (node (ref "L2") (pin "P$1") (pinfunction "P$1_P$1") (pintype "passive"))
    )
    (net (code "69") (name "unconnected-(J1-SBU1-PadA8)") (class "Default")
      (node (ref "J1") (pin "A8") (pinfunction "SBU1_A8") (pintype "bidirectional"))
    )
    (net (code "70") (name "unconnected-(J1-SBU2-PadB8)") (class "Default")
      (node (ref "J1") (pin "B8") (pinfunction "SBU2_B8") (pintype "bidirectional"))
    )
    (net (code "71") (name "unconnected-(J4-A0-Pad10)") (class "Default")
      (node (ref "J4") (pin "10") (pinfunction "A0_10") (pintype "bidirectional"))
    )
    (net (code "72") (name "unconnected-(J4-A1-Pad12)") (class "Default")
      (node (ref "J4") (pin "12") (pinfunction "A1_12") (pintype "bidirectional"))
    )
    (net (code "73") (name "unconnected-(J4-C0-Pad9)") (class "Default")
      (node (ref "J4") (pin "9") (pinfunction "C0_9") (pintype "bidirectional"))
    )
    (net (code "74") (name "unconnected-(J4-C1-Pad11)") (class "Default")
      (node (ref "J4") (pin "11") (pinfunction "C1_11") (pintype "bidirectional"))
    )
    (net (code "75") (name "unconnected-(J4-Pad7)") (class "Default")
      (node (ref "J4") (pin "7") (pinfunction "7_7") (pintype "bidirectional"))
    )
    (net (code "76") (name "unconnected-(J4-Pad8)") (class "Default")
      (node (ref "J4") (pin "8") (pinfunction "8_8") (pintype "bidirectional"))
    )
    (net (code "77") (name "unconnected-(SW1-PadP$2)") (class "Default")
      (node (ref "SW1") (pin "P$2") (pinfunction "P$2_P$2") (pintype "bidirectional"))
    )
    (net (code "78") (name "unconnected-(SW1-PadP$4)") (class "Default")
      (node (ref "SW1") (pin "P$4") (pinfunction "P$4_P$4") (pintype "bidirectional"))
    )
    (net (code "79") (name "unconnected-(U3-PG-Pad3)") (class "Default")
      (node (ref "U3") (pin "3") (pinfunction "PG_3") (pintype "bidirectional"))
    )
  )
)
